# 2_cyber60-mxhs_matrix.net
KiCad netlist of a schematic drawn in Altium Designer
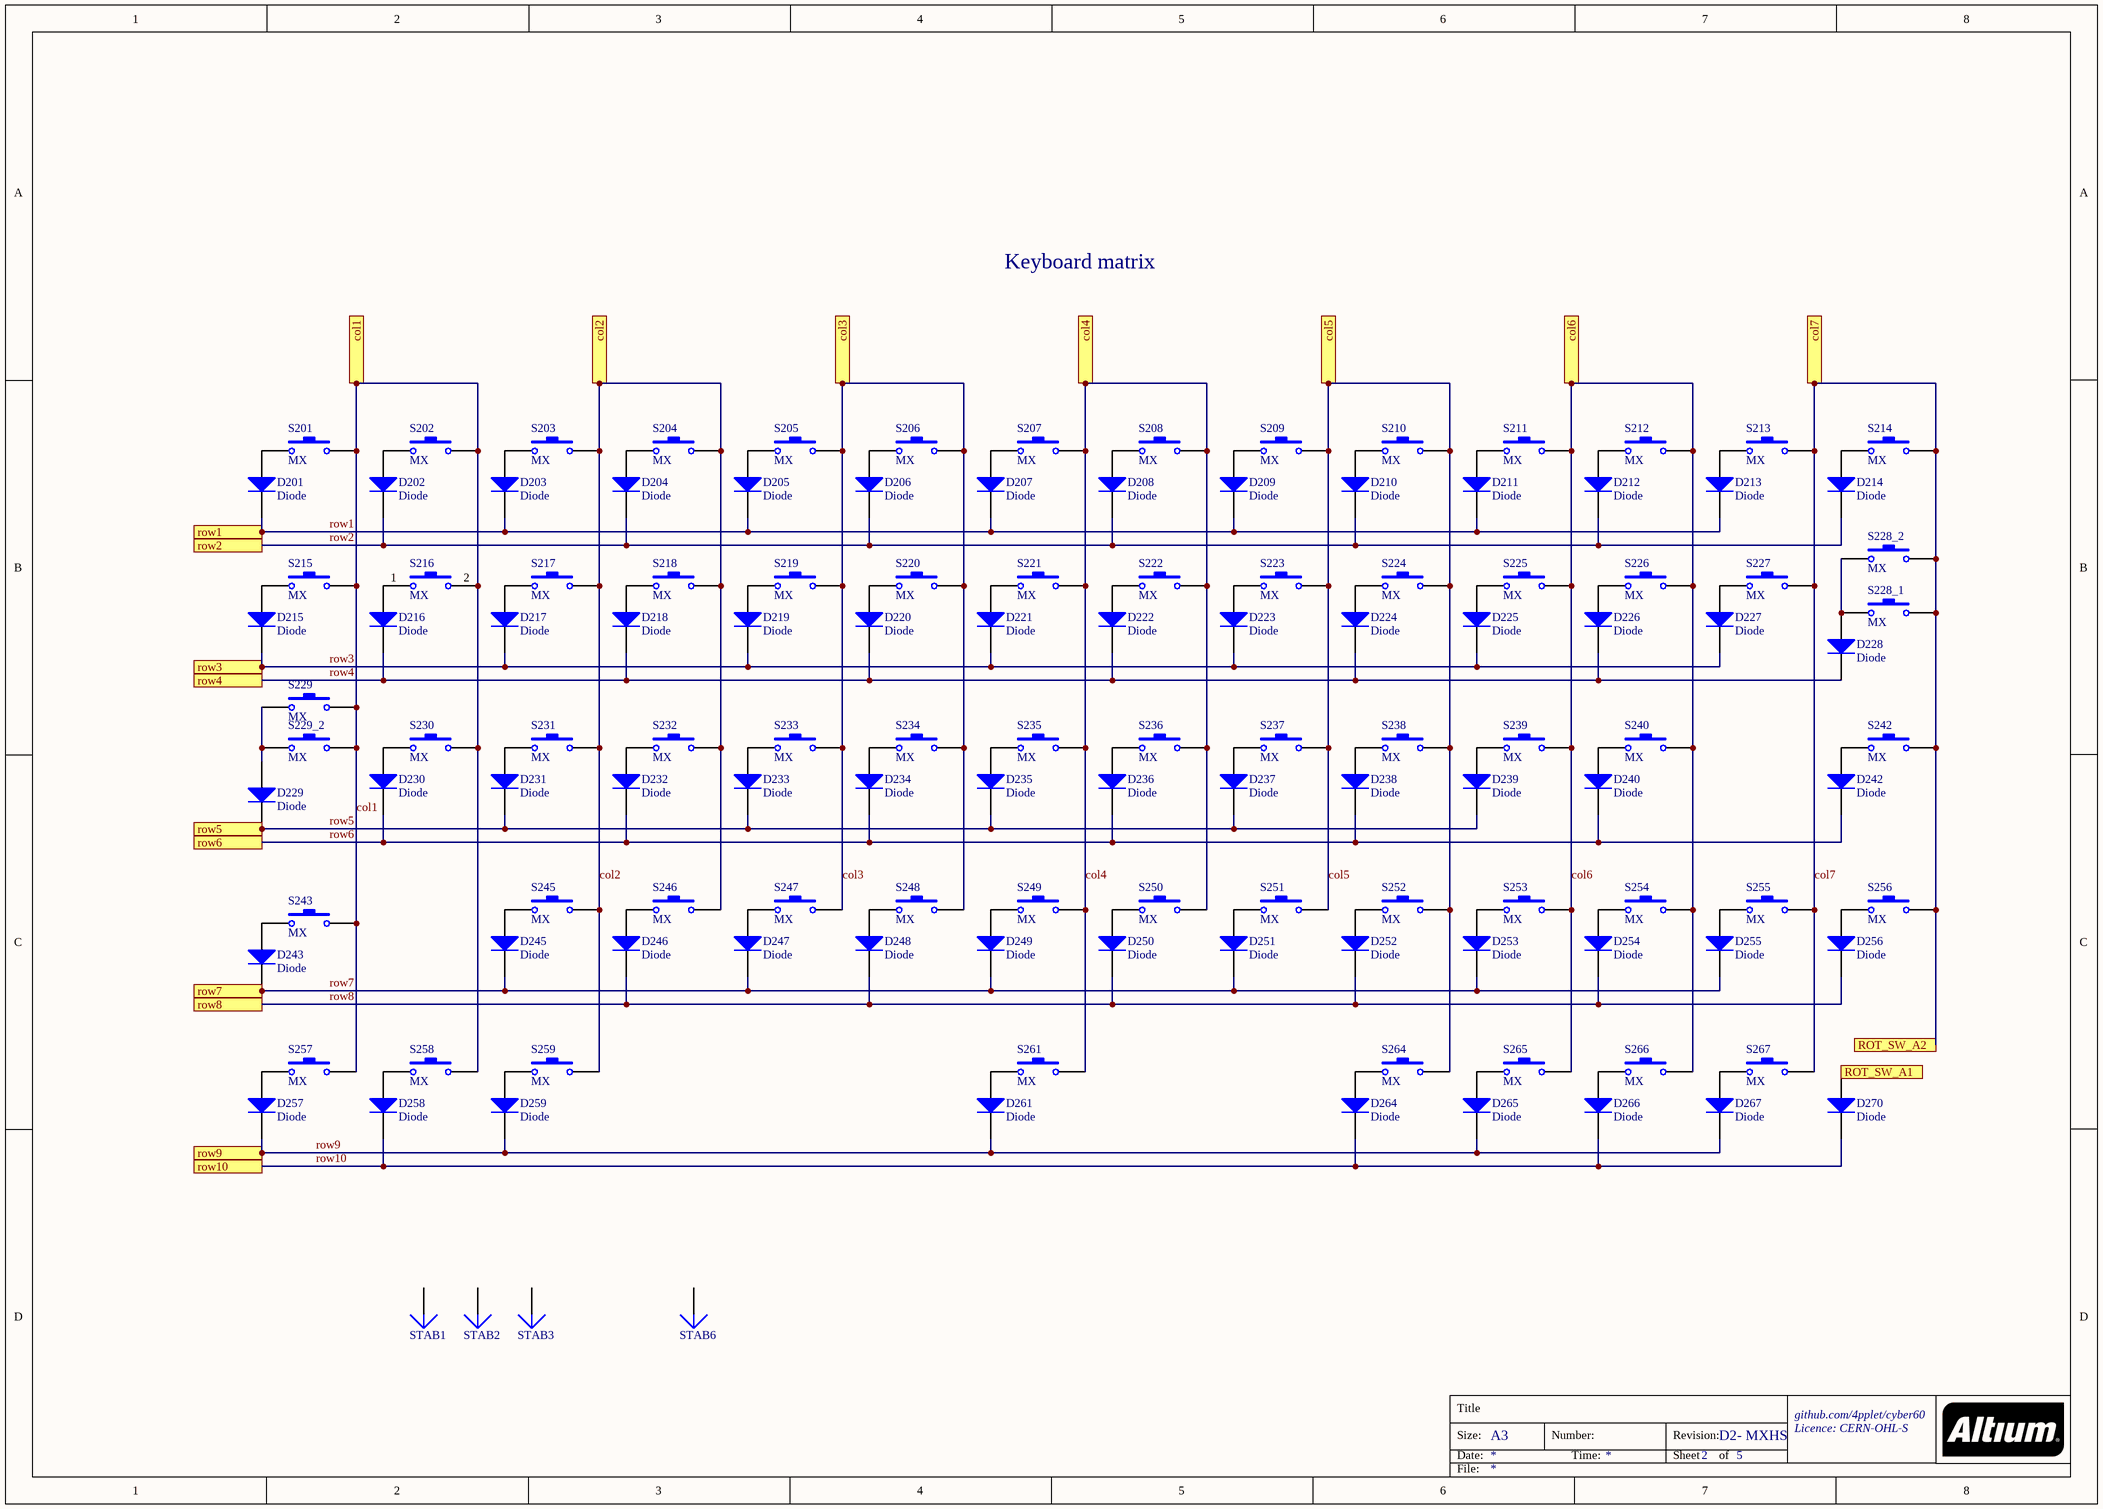
[diagram p0: 2_cyber60-mxhs_matrix.SchDoc]

(export (version "E")
  (design (tool "Eeschema 10.0.6"))
  (components
    (comp (ref "D201")
      (value "Diode")
      (footprint "SOD-123")
      (description "Default Diode")
      (fields (field (name "LCSC PART #") "C81598") (field (name "MRF.PART") "1N4148W"))
      (libsource (lib "Miscellaneous Devices") (part "Diode"))
    )
    (comp (ref "D202")
      (value "Diode")
      (footprint "SOD-123")
      (description "Default Diode")
      (fields (field (name "LCSC PART #") "C81598") (field (name "MRF.PART") "1N4148W"))
      (libsource (lib "Miscellaneous Devices") (part "Diode"))
    )
    (comp (ref "D203")
      (value "Diode")
      (footprint "SOD-123")
      (description "Default Diode")
      (fields (field (name "LCSC PART #") "C81598") (field (name "MRF.PART") "1N4148W"))
      (libsource (lib "Miscellaneous Devices") (part "Diode"))
    )
    (comp (ref "D204")
      (value "Diode")
      (footprint "SOD-123")
      (description "Default Diode")
      (fields (field (name "LCSC PART #") "C81598") (field (name "MRF.PART") "1N4148W"))
      (libsource (lib "Miscellaneous Devices") (part "Diode"))
    )
    (comp (ref "D205")
      (value "Diode")
      (footprint "SOD-123")
      (description "Default Diode")
      (fields (field (name "LCSC PART #") "C81598") (field (name "MRF.PART") "1N4148W"))
      (libsource (lib "Miscellaneous Devices") (part "Diode"))
    )
    (comp (ref "D206")
      (value "Diode")
      (footprint "SOD-123")
      (description "Default Diode")
      (fields (field (name "LCSC PART #") "C81598") (field (name "MRF.PART") "1N4148W"))
      (libsource (lib "Miscellaneous Devices") (part "Diode"))
    )
    (comp (ref "D207")
      (value "Diode")
      (footprint "SOD-123")
      (description "Default Diode")
      (fields (field (name "LCSC PART #") "C81598") (field (name "MRF.PART") "1N4148W"))
      (libsource (lib "Miscellaneous Devices") (part "Diode"))
    )
    (comp (ref "D208")
      (value "Diode")
      (footprint "SOD-123")
      (description "Default Diode")
      (fields (field (name "LCSC PART #") "C81598") (field (name "MRF.PART") "1N4148W"))
      (libsource (lib "Miscellaneous Devices") (part "Diode"))
    )
    (comp (ref "D209")
      (value "Diode")
      (footprint "SOD-123")
      (description "Default Diode")
      (fields (field (name "LCSC PART #") "C81598") (field (name "MRF.PART") "1N4148W"))
      (libsource (lib "Miscellaneous Devices") (part "Diode"))
    )
    (comp (ref "D210")
      (value "Diode")
      (footprint "SOD-123")
      (description "Default Diode")
      (fields (field (name "LCSC PART #") "C81598") (field (name "MRF.PART") "1N4148W"))
      (libsource (lib "Miscellaneous Devices") (part "Diode"))
    )
    (comp (ref "D211")
      (value "Diode")
      (footprint "SOD-123")
      (description "Default Diode")
      (fields (field (name "LCSC PART #") "C81598") (field (name "MRF.PART") "1N4148W"))
      (libsource (lib "Miscellaneous Devices") (part "Diode"))
    )
    (comp (ref "D212")
      (value "Diode")
      (footprint "SOD-123")
      (description "Default Diode")
      (fields (field (name "LCSC PART #") "C81598") (field (name "MRF.PART") "1N4148W"))
      (libsource (lib "Miscellaneous Devices") (part "Diode"))
    )
    (comp (ref "D213")
      (value "Diode")
      (footprint "SOD-123")
      (description "Default Diode")
      (fields (field (name "LCSC PART #") "C81598") (field (name "MRF.PART") "1N4148W"))
      (libsource (lib "Miscellaneous Devices") (part "Diode"))
    )
    (comp (ref "D214")
      (value "Diode")
      (footprint "SOD-123")
      (description "Default Diode")
      (fields (field (name "LCSC PART #") "C81598") (field (name "MRF.PART") "1N4148W"))
      (libsource (lib "Miscellaneous Devices") (part "Diode"))
    )
    (comp (ref "D215")
      (value "Diode")
      (footprint "SOD-123")
      (description "Default Diode")
      (fields (field (name "LCSC PART #") "C81598") (field (name "MRF.PART") "1N4148W"))
      (libsource (lib "Miscellaneous Devices") (part "Diode"))
    )
    (comp (ref "D216")
      (value "Diode")
      (footprint "SOD-123")
      (description "Default Diode")
      (fields (field (name "LCSC PART #") "C81598") (field (name "MRF.PART") "1N4148W"))
      (libsource (lib "Miscellaneous Devices") (part "Diode"))
    )
    (comp (ref "D217")
      (value "Diode")
      (footprint "SOD-123")
      (description "Default Diode")
      (fields (field (name "LCSC PART #") "C81598") (field (name "MRF.PART") "1N4148W"))
      (libsource (lib "Miscellaneous Devices") (part "Diode"))
    )
    (comp (ref "D218")
      (value "Diode")
      (footprint "SOD-123")
      (description "Default Diode")
      (fields (field (name "LCSC PART #") "C81598") (field (name "MRF.PART") "1N4148W"))
      (libsource (lib "Miscellaneous Devices") (part "Diode"))
    )
    (comp (ref "D219")
      (value "Diode")
      (footprint "SOD-123")
      (description "Default Diode")
      (fields (field (name "LCSC PART #") "C81598") (field (name "MRF.PART") "1N4148W"))
      (libsource (lib "Miscellaneous Devices") (part "Diode"))
    )
    (comp (ref "D220")
      (value "Diode")
      (footprint "SOD-123")
      (description "Default Diode")
      (fields (field (name "LCSC PART #") "C81598") (field (name "MRF.PART") "1N4148W"))
      (libsource (lib "Miscellaneous Devices") (part "Diode"))
    )
    (comp (ref "D221")
      (value "Diode")
      (footprint "SOD-123")
      (description "Default Diode")
      (fields (field (name "LCSC PART #") "C81598") (field (name "MRF.PART") "1N4148W"))
      (libsource (lib "Miscellaneous Devices") (part "Diode"))
    )
    (comp (ref "D222")
      (value "Diode")
      (footprint "SOD-123")
      (description "Default Diode")
      (fields (field (name "LCSC PART #") "C81598") (field (name "MRF.PART") "1N4148W"))
      (libsource (lib "Miscellaneous Devices") (part "Diode"))
    )
    (comp (ref "D223")
      (value "Diode")
      (footprint "SOD-123")
      (description "Default Diode")
      (fields (field (name "LCSC PART #") "C81598") (field (name "MRF.PART") "1N4148W"))
      (libsource (lib "Miscellaneous Devices") (part "Diode"))
    )
    (comp (ref "D224")
      (value "Diode")
      (footprint "SOD-123")
      (description "Default Diode")
      (fields (field (name "LCSC PART #") "C81598") (field (name "MRF.PART") "1N4148W"))
      (libsource (lib "Miscellaneous Devices") (part "Diode"))
    )
    (comp (ref "D225")
      (value "Diode")
      (footprint "SOD-123")
      (description "Default Diode")
      (fields (field (name "LCSC PART #") "C81598") (field (name "MRF.PART") "1N4148W"))
      (libsource (lib "Miscellaneous Devices") (part "Diode"))
    )
    (comp (ref "D226")
      (value "Diode")
      (footprint "SOD-123")
      (description "Default Diode")
      (fields (field (name "LCSC PART #") "C81598") (field (name "MRF.PART") "1N4148W"))
      (libsource (lib "Miscellaneous Devices") (part "Diode"))
    )
    (comp (ref "D227")
      (value "Diode")
      (footprint "SOD-123")
      (description "Default Diode")
      (fields (field (name "LCSC PART #") "C81598") (field (name "MRF.PART") "1N4148W"))
      (libsource (lib "Miscellaneous Devices") (part "Diode"))
    )
    (comp (ref "D228")
      (value "Diode")
      (footprint "SOD-123")
      (description "Default Diode")
      (fields (field (name "LCSC PART #") "C81598") (field (name "MRF.PART") "1N4148W"))
      (libsource (lib "Miscellaneous Devices") (part "Diode"))
    )
    (comp (ref "D229")
      (value "Diode")
      (footprint "SOD-123")
      (description "Default Diode")
      (fields (field (name "LCSC PART #") "C81598") (field (name "MRF.PART") "1N4148W"))
      (libsource (lib "Miscellaneous Devices") (part "Diode"))
    )
    (comp (ref "D230")
      (value "Diode")
      (footprint "SOD-123")
      (description "Default Diode")
      (fields (field (name "LCSC PART #") "C81598") (field (name "MRF.PART") "1N4148W"))
      (libsource (lib "Miscellaneous Devices") (part "Diode"))
    )
    (comp (ref "D231")
      (value "Diode")
      (footprint "SOD-123")
      (description "Default Diode")
      (fields (field (name "LCSC PART #") "C81598") (field (name "MRF.PART") "1N4148W"))
      (libsource (lib "Miscellaneous Devices") (part "Diode"))
    )
    (comp (ref "D232")
      (value "Diode")
      (footprint "SOD-123")
      (description "Default Diode")
      (fields (field (name "LCSC PART #") "C81598") (field (name "MRF.PART") "1N4148W"))
      (libsource (lib "Miscellaneous Devices") (part "Diode"))
    )
    (comp (ref "D233")
      (value "Diode")
      (footprint "SOD-123")
      (description "Default Diode")
      (fields (field (name "LCSC PART #") "C81598") (field (name "MRF.PART") "1N4148W"))
      (libsource (lib "Miscellaneous Devices") (part "Diode"))
    )
    (comp (ref "D234")
      (value "Diode")
      (footprint "SOD-123")
      (description "Default Diode")
      (fields (field (name "LCSC PART #") "C81598") (field (name "MRF.PART") "1N4148W"))
      (libsource (lib "Miscellaneous Devices") (part "Diode"))
    )
    (comp (ref "D235")
      (value "Diode")
      (footprint "SOD-123")
      (description "Default Diode")
      (fields (field (name "LCSC PART #") "C81598") (field (name "MRF.PART") "1N4148W"))
      (libsource (lib "Miscellaneous Devices") (part "Diode"))
    )
    (comp (ref "D236")
      (value "Diode")
      (footprint "SOD-123")
      (description "Default Diode")
      (fields (field (name "LCSC PART #") "C81598") (field (name "MRF.PART") "1N4148W"))
      (libsource (lib "Miscellaneous Devices") (part "Diode"))
    )
    (comp (ref "D237")
      (value "Diode")
      (footprint "SOD-123")
      (description "Default Diode")
      (fields (field (name "LCSC PART #") "C81598") (field (name "MRF.PART") "1N4148W"))
      (libsource (lib "Miscellaneous Devices") (part "Diode"))
    )
    (comp (ref "D238")
      (value "Diode")
      (footprint "SOD-123")
      (description "Default Diode")
      (fields (field (name "LCSC PART #") "C81598") (field (name "MRF.PART") "1N4148W"))
      (libsource (lib "Miscellaneous Devices") (part "Diode"))
    )
    (comp (ref "D239")
      (value "Diode")
      (footprint "SOD-123")
      (description "Default Diode")
      (fields (field (name "LCSC PART #") "C81598") (field (name "MRF.PART") "1N4148W"))
      (libsource (lib "Miscellaneous Devices") (part "Diode"))
    )
    (comp (ref "D240")
      (value "Diode")
      (footprint "SOD-123")
      (description "Default Diode")
      (fields (field (name "LCSC PART #") "C81598") (field (name "MRF.PART") "1N4148W"))
      (libsource (lib "Miscellaneous Devices") (part "Diode"))
    )
    (comp (ref "D242")
      (value "Diode")
      (footprint "SOD-123")
      (description "Default Diode")
      (fields (field (name "LCSC PART #") "C81598") (field (name "MRF.PART") "1N4148W"))
      (libsource (lib "Miscellaneous Devices") (part "Diode"))
    )
    (comp (ref "D243")
      (value "Diode")
      (footprint "SOD-123")
      (description "Default Diode")
      (fields (field (name "LCSC PART #") "C81598") (field (name "MRF.PART") "1N4148W"))
      (libsource (lib "Miscellaneous Devices") (part "Diode"))
    )
    (comp (ref "D245")
      (value "Diode")
      (footprint "SOD-123")
      (description "Default Diode")
      (fields (field (name "LCSC PART #") "C81598") (field (name "MRF.PART") "1N4148W"))
      (libsource (lib "Miscellaneous Devices") (part "Diode"))
    )
    (comp (ref "D246")
      (value "Diode")
      (footprint "SOD-123")
      (description "Default Diode")
      (fields (field (name "LCSC PART #") "C81598") (field (name "MRF.PART") "1N4148W"))
      (libsource (lib "Miscellaneous Devices") (part "Diode"))
    )
    (comp (ref "D247")
      (value "Diode")
      (footprint "SOD-123")
      (description "Default Diode")
      (fields (field (name "LCSC PART #") "C81598") (field (name "MRF.PART") "1N4148W"))
      (libsource (lib "Miscellaneous Devices") (part "Diode"))
    )
    (comp (ref "D248")
      (value "Diode")
      (footprint "SOD-123")
      (description "Default Diode")
      (fields (field (name "LCSC PART #") "C81598") (field (name "MRF.PART") "1N4148W"))
      (libsource (lib "Miscellaneous Devices") (part "Diode"))
    )
    (comp (ref "D249")
      (value "Diode")
      (footprint "SOD-123")
      (description "Default Diode")
      (fields (field (name "LCSC PART #") "C81598") (field (name "MRF.PART") "1N4148W"))
      (libsource (lib "Miscellaneous Devices") (part "Diode"))
    )
    (comp (ref "D250")
      (value "Diode")
      (footprint "SOD-123")
      (description "Default Diode")
      (fields (field (name "LCSC PART #") "C81598") (field (name "MRF.PART") "1N4148W"))
      (libsource (lib "Miscellaneous Devices") (part "Diode"))
    )
    (comp (ref "D251")
      (value "Diode")
      (footprint "SOD-123")
      (description "Default Diode")
      (fields (field (name "LCSC PART #") "C81598") (field (name "MRF.PART") "1N4148W"))
      (libsource (lib "Miscellaneous Devices") (part "Diode"))
    )
    (comp (ref "D252")
      (value "Diode")
      (footprint "SOD-123")
      (description "Default Diode")
      (fields (field (name "LCSC PART #") "C81598") (field (name "MRF.PART") "1N4148W"))
      (libsource (lib "Miscellaneous Devices") (part "Diode"))
    )
    (comp (ref "D253")
      (value "Diode")
      (footprint "SOD-123")
      (description "Default Diode")
      (fields (field (name "LCSC PART #") "C81598") (field (name "MRF.PART") "1N4148W"))
      (libsource (lib "Miscellaneous Devices") (part "Diode"))
    )
    (comp (ref "D254")
      (value "Diode")
      (footprint "SOD-123")
      (description "Default Diode")
      (fields (field (name "LCSC PART #") "C81598") (field (name "MRF.PART") "1N4148W"))
      (libsource (lib "Miscellaneous Devices") (part "Diode"))
    )
    (comp (ref "D255")
      (value "Diode")
      (footprint "SOD-123")
      (description "Default Diode")
      (fields (field (name "LCSC PART #") "C81598") (field (name "MRF.PART") "1N4148W"))
      (libsource (lib "Miscellaneous Devices") (part "Diode"))
    )
    (comp (ref "D256")
      (value "Diode")
      (footprint "SOD-123")
      (description "Default Diode")
      (fields (field (name "LCSC PART #") "C81598") (field (name "MRF.PART") "1N4148W"))
      (libsource (lib "Miscellaneous Devices") (part "Diode"))
    )
    (comp (ref "D257")
      (value "Diode")
      (footprint "SOD-123")
      (description "Default Diode")
      (fields (field (name "LCSC PART #") "C81598") (field (name "MRF.PART") "1N4148W"))
      (libsource (lib "Miscellaneous Devices") (part "Diode"))
    )
    (comp (ref "D258")
      (value "Diode")
      (footprint "SOD-123")
      (description "Default Diode")
      (fields (field (name "LCSC PART #") "C81598") (field (name "MRF.PART") "1N4148W"))
      (libsource (lib "Miscellaneous Devices") (part "Diode"))
    )
    (comp (ref "D259")
      (value "Diode")
      (footprint "SOD-123")
      (description "Default Diode")
      (fields (field (name "LCSC PART #") "C81598") (field (name "MRF.PART") "1N4148W"))
      (libsource (lib "Miscellaneous Devices") (part "Diode"))
    )
    (comp (ref "D261")
      (value "Diode")
      (footprint "SOD-123")
      (description "Default Diode")
      (fields (field (name "LCSC PART #") "C81598") (field (name "MRF.PART") "1N4148W"))
      (libsource (lib "Miscellaneous Devices") (part "Diode"))
    )
    (comp (ref "D264")
      (value "Diode")
      (footprint "SOD-123")
      (description "Default Diode")
      (fields (field (name "LCSC PART #") "C81598") (field (name "MRF.PART") "1N4148W"))
      (libsource (lib "Miscellaneous Devices") (part "Diode"))
    )
    (comp (ref "D265")
      (value "Diode")
      (footprint "SOD-123")
      (description "Default Diode")
      (fields (field (name "LCSC PART #") "C81598") (field (name "MRF.PART") "1N4148W"))
      (libsource (lib "Miscellaneous Devices") (part "Diode"))
    )
    (comp (ref "D266")
      (value "Diode")
      (footprint "SOD-123")
      (description "Default Diode")
      (fields (field (name "LCSC PART #") "C81598") (field (name "MRF.PART") "1N4148W"))
      (libsource (lib "Miscellaneous Devices") (part "Diode"))
    )
    (comp (ref "D267")
      (value "Diode")
      (footprint "SOD-123")
      (description "Default Diode")
      (fields (field (name "LCSC PART #") "C81598") (field (name "MRF.PART") "1N4148W"))
      (libsource (lib "Miscellaneous Devices") (part "Diode"))
    )
    (comp (ref "D270")
      (value "Diode")
      (footprint "SOD-123")
      (description "Default Diode")
      (fields (field (name "LCSC PART #") "C81598") (field (name "MRF.PART") "1N4148W"))
      (libsource (lib "Miscellaneous Devices") (part "Diode"))
    )
    (comp (ref "S201")
      (value "MX")
      (footprint "MXHS-switch - 1U Top layer - switched pol AS2")
      (description "Switch")
      (fields (field (name "LCSC PART #") "C2803348") (field (name "MRF.PART") "CPG151101S11"))
      (libsource (lib "Miscellaneous Devices") (part "SW-PB"))
    )
    (comp (ref "S202")
      (value "MX")
      (footprint "MXHS-switch - 1U Top layer - switched pol AS2")
      (description "Switch")
      (fields (field (name "LCSC PART #") "C2803348") (field (name "MRF.PART") "CPG151101S11"))
      (libsource (lib "Miscellaneous Devices") (part "SW-PB"))
    )
    (comp (ref "S203")
      (value "MX")
      (footprint "MXHS-switch - 1U Top layer - AS2")
      (description "Switch")
      (fields (field (name "LCSC PART #") "C2803348") (field (name "MRF.PART") "CPG151101S11"))
      (libsource (lib "Miscellaneous Devices") (part "SW-PB"))
    )
    (comp (ref "S204")
      (value "MX")
      (footprint "MXHS-switch - 1U Top layer - switched pol AS2")
      (description "Switch")
      (fields (field (name "LCSC PART #") "C2803348") (field (name "MRF.PART") "CPG151101S11"))
      (libsource (lib "Miscellaneous Devices") (part "SW-PB"))
    )
    (comp (ref "S205")
      (value "MX")
      (footprint "MXHS-switch - 1U Top layer - AS2")
      (description "Switch")
      (fields (field (name "LCSC PART #") "C2803348") (field (name "MRF.PART") "CPG151101S11"))
      (libsource (lib "Miscellaneous Devices") (part "SW-PB"))
    )
    (comp (ref "S206")
      (value "MX")
      (footprint "MXHS-switch - 1U Top layer - AS2")
      (description "Switch")
      (fields (field (name "LCSC PART #") "C2803348") (field (name "MRF.PART") "CPG151101S11"))
      (libsource (lib "Miscellaneous Devices") (part "SW-PB"))
    )
    (comp (ref "S207")
      (value "MX")
      (footprint "MXHS-switch - 1U Top layer - AS2")
      (description "Switch")
      (fields (field (name "LCSC PART #") "C2803348") (field (name "MRF.PART") "CPG151101S11"))
      (libsource (lib "Miscellaneous Devices") (part "SW-PB"))
    )
    (comp (ref "S208")
      (value "MX")
      (footprint "MXHS-switch - 1U Top layer - AS2")
      (description "Switch")
      (fields (field (name "LCSC PART #") "C2803348") (field (name "MRF.PART") "CPG151101S11"))
      (libsource (lib "Miscellaneous Devices") (part "SW-PB"))
    )
    (comp (ref "S209")
      (value "MX")
      (footprint "MXHS-switch - 1U Top layer - AS2")
      (description "Switch")
      (fields (field (name "LCSC PART #") "C2803348") (field (name "MRF.PART") "CPG151101S11"))
      (libsource (lib "Miscellaneous Devices") (part "SW-PB"))
    )
    (comp (ref "S210")
      (value "MX")
      (footprint "MXHS-switch - 1U Top layer - switched pol AS2")
      (description "Switch")
      (fields (field (name "LCSC PART #") "C2803348") (field (name "MRF.PART") "CPG151101S11"))
      (libsource (lib "Miscellaneous Devices") (part "SW-PB"))
    )
    (comp (ref "S211")
      (value "MX")
      (footprint "MXHS-switch - 1U Top layer - AS2")
      (description "Switch")
      (fields (field (name "LCSC PART #") "C2803348") (field (name "MRF.PART") "CPG151101S11"))
      (libsource (lib "Miscellaneous Devices") (part "SW-PB"))
    )
    (comp (ref "S212")
      (value "MX")
      (footprint "MXHS-switch - 1U Top layer - AS2")
      (description "Switch")
      (fields (field (name "LCSC PART #") "C2803348") (field (name "MRF.PART") "CPG151101S11"))
      (libsource (lib "Miscellaneous Devices") (part "SW-PB"))
    )
    (comp (ref "S213")
      (value "MX")
      (footprint "MXHS-switch - 1U Top layer - switched pol AS2")
      (description "Switch")
      (fields (field (name "LCSC PART #") "C2803348") (field (name "MRF.PART") "CPG151101S11"))
      (libsource (lib "Miscellaneous Devices") (part "SW-PB"))
    )
    (comp (ref "S214")
      (value "MX")
      (footprint "MXHS-switch - 1U Top layer - AS2 - S2")
      (description "Switch")
      (fields (field (name "LCSC PART #") "C2803348") (field (name "MRF.PART") "CPG151101S11"))
      (libsource (lib "Miscellaneous Devices") (part "SW-PB"))
    )
    (comp (ref "S215")
      (value "MX")
      (footprint "MXHS-switch - 1U Top layer - switched pol AS2")
      (description "TAB")
      (fields (field (name "LCSC PART #") "C2803348") (field (name "MRF.PART") "CPG151101S11"))
      (libsource (lib "Miscellaneous Devices") (part "SW-PB"))
    )
    (comp (ref "S216")
      (value "MX")
      (footprint "MXHS-switch - 1U Top layer - AS2 - S1")
      (description "Switch")
      (fields (field (name "LCSC PART #") "C2803348") (field (name "MRF.PART") "CPG151101S11"))
      (libsource (lib "") (part "SW-PB_1"))
    )
    (comp (ref "S217")
      (value "MX")
      (footprint "MXHS-switch - 1U Top layer - AS2")
      (description "Switch")
      (fields (field (name "LCSC PART #") "C2803348") (field (name "MRF.PART") "CPG151101S11"))
      (libsource (lib "Miscellaneous Devices") (part "SW-PB"))
    )
    (comp (ref "S218")
      (value "MX")
      (footprint "MXHS-switch - 1U Top layer - AS2")
      (description "Switch")
      (fields (field (name "LCSC PART #") "C2803348") (field (name "MRF.PART") "CPG151101S11"))
      (libsource (lib "Miscellaneous Devices") (part "SW-PB"))
    )
    (comp (ref "S219")
      (value "MX")
      (footprint "MXHS-switch - 1U Top layer - AS2")
      (description "Switch")
      (fields (field (name "LCSC PART #") "C2803348") (field (name "MRF.PART") "CPG151101S11"))
      (libsource (lib "Miscellaneous Devices") (part "SW-PB"))
    )
    (comp (ref "S220")
      (value "MX")
      (footprint "MXHS-switch - 1U Top layer - switched pol AS2")
      (description "Switch")
      (fields (field (name "LCSC PART #") "C2803348") (field (name "MRF.PART") "CPG151101S11"))
      (libsource (lib "Miscellaneous Devices") (part "SW-PB"))
    )
    (comp (ref "S221")
      (value "MX")
      (footprint "MXHS-switch - 1U Top layer - switched pol AS2")
      (description "Switch")
      (fields (field (name "LCSC PART #") "C2803348") (field (name "MRF.PART") "CPG151101S11"))
      (libsource (lib "Miscellaneous Devices") (part "SW-PB"))
    )
    (comp (ref "S222")
      (value "MX")
      (footprint "MXHS-switch - 1U Top layer - AS2")
      (description "Switch")
      (fields (field (name "LCSC PART #") "C2803348") (field (name "MRF.PART") "CPG151101S11"))
      (libsource (lib "Miscellaneous Devices") (part "SW-PB"))
    )
    (comp (ref "S223")
      (value "MX")
      (footprint "MXHS-switch - 1U Top layer - AS2")
      (description "Switch")
      (fields (field (name "LCSC PART #") "C2803348") (field (name "MRF.PART") "CPG151101S11"))
      (libsource (lib "Miscellaneous Devices") (part "SW-PB"))
    )
    (comp (ref "S224")
      (value "MX")
      (footprint "MXHS-switch - 1U Top layer - AS2")
      (description "Switch")
      (fields (field (name "LCSC PART #") "C2803348") (field (name "MRF.PART") "CPG151101S11"))
      (libsource (lib "Miscellaneous Devices") (part "SW-PB"))
    )
    (comp (ref "S225")
      (value "MX")
      (footprint "MXHS-switch - 1U Top layer - AS2")
      (description "Switch")
      (fields (field (name "LCSC PART #") "C2803348") (field (name "MRF.PART") "CPG151101S11"))
      (libsource (lib "Miscellaneous Devices") (part "SW-PB"))
    )
    (comp (ref "S226")
      (value "MX")
      (footprint "MXHS-switch - 1U Top layer - switched pol AS2")
      (description "Switch")
      (fields (field (name "LCSC PART #") "C2803348") (field (name "MRF.PART") "CPG151101S11"))
      (libsource (lib "Miscellaneous Devices") (part "SW-PB"))
    )
    (comp (ref "S227")
      (value "MX")
      (footprint "MXHS-switch - 1U Top layer - switched pol AS2")
      (description "Switch")
      (fields (field (name "LCSC PART #") "C2803348") (field (name "MRF.PART") "CPG151101S11"))
      (libsource (lib "Miscellaneous Devices") (part "SW-PB"))
    )
    (comp (ref "S228_1")
      (value "MX")
      (footprint "MXHS-switch - 1U Top layer - AS2 - S1")
      (description "Switch")
      (fields (field (name "LCSC PART #") "C2803348") (field (name "MRF.PART") "CPG151101S11"))
      (libsource (lib "Miscellaneous Devices") (part "SW-PB"))
    )
    (comp (ref "S228_2")
      (value "MX")
      (footprint "MXHS-switch - 1U Top layer - AS2 - S2")
      (description "Switch")
      (fields (field (name "LCSC PART #") "C2803348") (field (name "MRF.PART") "CPG151101S11"))
      (libsource (lib "Miscellaneous Devices") (part "SW-PB"))
    )
    (comp (ref "S229")
      (value "MX")
      (footprint "MXHS-switch - 1U Top layer - AS2")
      (description "Switch")
      (fields (field (name "LCSC PART #") "C2803348") (field (name "MRF.PART") "CPG151101S11"))
      (libsource (lib "Miscellaneous Devices") (part "SW-PB"))
    )
    (comp (ref "S229_2")
      (value "MX")
      (footprint "MXHS-switch - 1U Top layer - switched pol AS2")
      (description "Switch")
      (fields (field (name "LCSC PART #") "C2803348") (field (name "MRF.PART") "CPG151101S11"))
      (libsource (lib "Miscellaneous Devices") (part "SW-PB"))
    )
    (comp (ref "S230")
      (value "MX")
      (footprint "MXHS-switch - 1U Top layer - AS2")
      (description "Switch")
      (fields (field (name "LCSC PART #") "C2803348") (field (name "MRF.PART") "CPG151101S11"))
      (libsource (lib "Miscellaneous Devices") (part "SW-PB"))
    )
    (comp (ref "S231")
      (value "MX")
      (footprint "MXHS-switch - 1U Top layer - AS2")
      (description "Switch")
      (fields (field (name "LCSC PART #") "C2803348") (field (name "MRF.PART") "CPG151101S11"))
      (libsource (lib "Miscellaneous Devices") (part "SW-PB"))
    )
    (comp (ref "S232")
      (value "MX")
      (footprint "MXHS-switch - 1U Top layer - AS2")
      (description "Switch")
      (fields (field (name "LCSC PART #") "C2803348") (field (name "MRF.PART") "CPG151101S11"))
      (libsource (lib "Miscellaneous Devices") (part "SW-PB"))
    )
    (comp (ref "S233")
      (value "MX")
      (footprint "MXHS-switch - 1U Top layer - AS2")
      (description "Switch")
      (fields (field (name "LCSC PART #") "C2803348") (field (name "MRF.PART") "CPG151101S11"))
      (libsource (lib "Miscellaneous Devices") (part "SW-PB"))
    )
    (comp (ref "S234")
      (value "MX")
      (footprint "MXHS-switch - 1U Top layer - switched pol AS2")
      (description "Switch")
      (fields (field (name "LCSC PART #") "C2803348") (field (name "MRF.PART") "CPG151101S11"))
      (libsource (lib "Miscellaneous Devices") (part "SW-PB"))
    )
    (comp (ref "S235")
      (value "MX")
      (footprint "MXHS-switch - 1U Top layer - AS2 - S2")
      (description "Switch")
      (fields (field (name "LCSC PART #") "C2803348") (field (name "MRF.PART") "CPG151101S11"))
      (libsource (lib "Miscellaneous Devices") (part "SW-PB"))
    )
    (comp (ref "S236")
      (value "MX")
      (footprint "MXHS-switch - 1U Top layer - AS2")
      (description "Switch")
      (fields (field (name "LCSC PART #") "C2803348") (field (name "MRF.PART") "CPG151101S11"))
      (libsource (lib "Miscellaneous Devices") (part "SW-PB"))
    )
    (comp (ref "S237")
      (value "MX")
      (footprint "MXHS-switch - 1U Top layer - AS2")
      (description "Switch")
      (fields (field (name "LCSC PART #") "C2803348") (field (name "MRF.PART") "CPG151101S11"))
      (libsource (lib "Miscellaneous Devices") (part "SW-PB"))
    )
    (comp (ref "S238")
      (value "MX")
      (footprint "MXHS-switch - 1U Top layer - AS2")
      (description "Switch")
      (fields (field (name "LCSC PART #") "C2803348") (field (name "MRF.PART") "CPG151101S11"))
      (libsource (lib "Miscellaneous Devices") (part "SW-PB"))
    )
    (comp (ref "S239")
      (value "MX")
      (footprint "MXHS-switch - 1U Top layer - switched pol AS2")
      (description "Switch")
      (fields (field (name "LCSC PART #") "C2803348") (field (name "MRF.PART") "CPG151101S11"))
      (libsource (lib "Miscellaneous Devices") (part "SW-PB"))
    )
    (comp (ref "S240")
      (value "MX")
      (footprint "MXHS-switch - 1U Top layer - AS2")
      (description "Switch")
      (fields (field (name "LCSC PART #") "C2803348") (field (name "MRF.PART") "CPG151101S11"))
      (libsource (lib "Miscellaneous Devices") (part "SW-PB"))
    )
    (comp (ref "S242")
      (value "MX")
      (footprint "MXHS-switch - 1U Top layer - AS2 - S2")
      (description "Switch")
      (fields (field (name "LCSC PART #") "C2803348") (field (name "MRF.PART") "CPG151101S11"))
      (libsource (lib "Miscellaneous Devices") (part "SW-PB"))
    )
    (comp (ref "S243")
      (value "MX")
      (footprint "MXHS-switch - 1U Top layer - AS2")
      (description "Switch")
      (fields (field (name "LCSC PART #") "C2803348") (field (name "MRF.PART") "CPG151101S11"))
      (libsource (lib "Miscellaneous Devices") (part "SW-PB"))
    )
    (comp (ref "S245")
      (value "MX")
      (footprint "MXHS-switch - 1U Top layer - AS2")
      (description "Switch")
      (fields (field (name "LCSC PART #") "C2803348") (field (name "MRF.PART") "CPG151101S11"))
      (libsource (lib "Miscellaneous Devices") (part "SW-PB"))
    )
    (comp (ref "S246")
      (value "MX")
      (footprint "MXHS-switch - 1U Top layer - AS2")
      (description "Switch")
      (fields (field (name "LCSC PART #") "C2803348") (field (name "MRF.PART") "CPG151101S11"))
      (libsource (lib "Miscellaneous Devices") (part "SW-PB"))
    )
    (comp (ref "S247")
      (value "MX")
      (footprint "MXHS-switch - 1U Top layer - AS2")
      (description "Switch")
      (fields (field (name "LCSC PART #") "C2803348") (field (name "MRF.PART") "CPG151101S11"))
      (libsource (lib "Miscellaneous Devices") (part "SW-PB"))
    )
    (comp (ref "S248")
      (value "MX")
      (footprint "MXHS-switch - 1U Top layer - switched pol AS2")
      (description "Switch")
      (fields (field (name "LCSC PART #") "C2803348") (field (name "MRF.PART") "CPG151101S11"))
      (libsource (lib "Miscellaneous Devices") (part "SW-PB"))
    )
    (comp (ref "S249")
      (value "MX")
      (footprint "MXHS-switch - 1U Top layer - switched pol AS2")
      (description "Switch")
      (fields (field (name "LCSC PART #") "C2803348") (field (name "MRF.PART") "CPG151101S11"))
      (libsource (lib "Miscellaneous Devices") (part "SW-PB"))
    )
    (comp (ref "S250")
      (value "MX")
      (footprint "MXHS-switch - 1U Top layer - switched pol AS2")
      (description "Switch")
      (fields (field (name "LCSC PART #") "C2803348") (field (name "MRF.PART") "CPG151101S11"))
      (libsource (lib "Miscellaneous Devices") (part "SW-PB"))
    )
    (comp (ref "S251")
      (value "MX")
      (footprint "MXHS-switch - 1U Top layer - AS2")
      (description "Switch")
      (fields (field (name "LCSC PART #") "C2803348") (field (name "MRF.PART") "CPG151101S11"))
      (libsource (lib "Miscellaneous Devices") (part "SW-PB"))
    )
    (comp (ref "S252")
      (value "MX")
      (footprint "MXHS-switch - 1U Top layer - AS2")
      (description "Switch")
      (fields (field (name "LCSC PART #") "C2803348") (field (name "MRF.PART") "CPG151101S11"))
      (libsource (lib "Miscellaneous Devices") (part "SW-PB"))
    )
    (comp (ref "S253")
      (value "MX")
      (footprint "MXHS-switch - 1U Top layer - AS2")
      (description "Switch")
      (fields (field (name "LCSC PART #") "C2803348") (field (name "MRF.PART") "CPG151101S11"))
      (libsource (lib "Miscellaneous Devices") (part "SW-PB"))
    )
    (comp (ref "S254")
      (value "MX")
      (footprint "MXHS-switch - 1U Top layer - AS2")
      (description "Switch")
      (fields (field (name "LCSC PART #") "C2803348") (field (name "MRF.PART") "CPG151101S11"))
      (libsource (lib "Miscellaneous Devices") (part "SW-PB"))
    )
    (comp (ref "S255")
      (value "MX")
      (footprint "MXHS-switch - 1U Top layer - switched pol AS2")
      (description "Switch")
      (fields (field (name "LCSC PART #") "C2803348") (field (name "MRF.PART") "CPG151101S11"))
      (libsource (lib "Miscellaneous Devices") (part "SW-PB"))
    )
    (comp (ref "S256")
      (value "MX")
      (footprint "MXHS-switch - 1U Top layer - switched pol AS2")
      (description "Switch")
      (fields (field (name "LCSC PART #") "C2803348") (field (name "MRF.PART") "CPG151101S11"))
      (libsource (lib "Miscellaneous Devices") (part "SW-PB"))
    )
    (comp (ref "S257")
      (value "MX")
      (footprint "MXHS-switch - 1U Top layer - AS2")
      (description "Switch")
      (fields (field (name "LCSC PART #") "C2803348") (field (name "MRF.PART") "CPG151101S11"))
      (libsource (lib "Miscellaneous Devices") (part "SW-PB"))
    )
    (comp (ref "S258")
      (value "MX")
      (footprint "MXHS-switch - 1U Top layer - AS2")
      (description "Switch")
      (fields (field (name "LCSC PART #") "C2803348") (field (name "MRF.PART") "CPG151101S11"))
      (libsource (lib "Miscellaneous Devices") (part "SW-PB"))
    )
    (comp (ref "S259")
      (value "MX")
      (footprint "MXHS-switch - 1U Top layer - AS2")
      (description "Switch")
      (fields (field (name "LCSC PART #") "C2803348") (field (name "MRF.PART") "CPG151101S11"))
      (libsource (lib "Miscellaneous Devices") (part "SW-PB"))
    )
    (comp (ref "S261")
      (value "MX")
      (footprint "MXHS-switch - 1U Top layer - AS2")
      (description "Switch")
      (fields (field (name "LCSC PART #") "C2803348") (field (name "MRF.PART") "CPG151101S11"))
      (libsource (lib "Miscellaneous Devices") (part "SW-PB"))
    )
    (comp (ref "S264")
      (value "MX")
      (footprint "MXHS-switch - 1U Top layer - switched pol AS2")
      (description "Switch")
      (fields (field (name "LCSC PART #") "C2803348") (field (name "MRF.PART") "CPG151101S11"))
      (libsource (lib "Miscellaneous Devices") (part "SW-PB"))
    )
    (comp (ref "S265")
      (value "MX")
      (footprint "MXHS-switch - 1U Top layer - switched pol AS2")
      (description "Switch")
      (fields (field (name "LCSC PART #") "C2803348") (field (name "MRF.PART") "CPG151101S11"))
      (libsource (lib "Miscellaneous Devices") (part "SW-PB"))
    )
    (comp (ref "S266")
      (value "MX")
      (footprint "MXHS-switch - 1U Top layer - switched pol AS2")
      (description "Switch")
      (fields (field (name "LCSC PART #") "C2803348") (field (name "MRF.PART") "CPG151101S11"))
      (libsource (lib "Miscellaneous Devices") (part "SW-PB"))
    )
    (comp (ref "S267")
      (value "MX")
      (footprint "MXHS-switch - 1U Top layer - AS2")
      (description "Switch")
      (fields (field (name "LCSC PART #") "C2803348") (field (name "MRF.PART") "CPG151101S11"))
      (libsource (lib "Miscellaneous Devices") (part "SW-PB"))
    )
    (comp (ref "STAB1")
      (value "Plug")
      (footprint "Stab 2u")
      (libsource (lib "Miscellaneous Connectors") (part "Plug"))
    )
    (comp (ref "STAB2")
      (value "Plug")
      (footprint "Stab 2u")
      (libsource (lib "Miscellaneous Connectors") (part "Plug"))
    )
    (comp (ref "STAB3")
      (value "Plug")
      (footprint "Stab 7U")
      (libsource (lib "Miscellaneous Connectors") (part "Plug"))
    )
    (comp (ref "STAB6")
      (value "Plug")
      (footprint "Stab 2u")
      (libsource (lib "Miscellaneous Connectors") (part "Plug"))
    )
  )
  (nets
    (net (code "1") (name "/ROT_SW_A1") (class "Default")
      (node (ref "D270") (pin "1") (pinfunction "A_1") (pintype "passive"))
    )
    (net (code "2") (name "/col1") (class "Default")
      (node (ref "S201") (pin "2") (pinfunction "2_2") (pintype "passive"))
      (node (ref "S202") (pin "2") (pinfunction "2_2") (pintype "passive"))
      (node (ref "S215") (pin "2") (pinfunction "2_2") (pintype "passive"))
      (node (ref "S216") (pin "2") (pinfunction "2_2") (pintype "passive"))
      (node (ref "S229") (pin "2") (pinfunction "2_2") (pintype "passive"))
      (node (ref "S229_2") (pin "2") (pinfunction "2_2") (pintype "passive"))
      (node (ref "S230") (pin "2") (pinfunction "2_2") (pintype "passive"))
      (node (ref "S243") (pin "2") (pinfunction "2_2") (pintype "passive"))
      (node (ref "S257") (pin "2") (pinfunction "2_2") (pintype "passive"))
      (node (ref "S258") (pin "2") (pinfunction "2_2") (pintype "passive"))
    )
    (net (code "3") (name "/col2") (class "Default")
      (node (ref "S203") (pin "2") (pinfunction "2_2") (pintype "passive"))
      (node (ref "S204") (pin "2") (pinfunction "2_2") (pintype "passive"))
      (node (ref "S217") (pin "2") (pinfunction "2_2") (pintype "passive"))
      (node (ref "S218") (pin "2") (pinfunction "2_2") (pintype "passive"))
      (node (ref "S231") (pin "2") (pinfunction "2_2") (pintype "passive"))
      (node (ref "S232") (pin "2") (pinfunction "2_2") (pintype "passive"))
      (node (ref "S245") (pin "2") (pinfunction "2_2") (pintype "passive"))
      (node (ref "S246") (pin "2") (pinfunction "2_2") (pintype "passive"))
      (node (ref "S259") (pin "2") (pinfunction "2_2") (pintype "passive"))
    )
    (net (code "4") (name "/col3") (class "Default")
      (node (ref "S205") (pin "2") (pinfunction "2_2") (pintype "passive"))
      (node (ref "S206") (pin "2") (pinfunction "2_2") (pintype "passive"))
      (node (ref "S219") (pin "2") (pinfunction "2_2") (pintype "passive"))
      (node (ref "S220") (pin "2") (pinfunction "2_2") (pintype "passive"))
      (node (ref "S233") (pin "2") (pinfunction "2_2") (pintype "passive"))
      (node (ref "S234") (pin "2") (pinfunction "2_2") (pintype "passive"))
      (node (ref "S247") (pin "2") (pinfunction "2_2") (pintype "passive"))
      (node (ref "S248") (pin "2") (pinfunction "2_2") (pintype "passive"))
    )
    (net (code "5") (name "/col4") (class "Default")
      (node (ref "S207") (pin "2") (pinfunction "2_2") (pintype "passive"))
      (node (ref "S208") (pin "2") (pinfunction "2_2") (pintype "passive"))
      (node (ref "S221") (pin "2") (pinfunction "2_2") (pintype "passive"))
      (node (ref "S222") (pin "2") (pinfunction "2_2") (pintype "passive"))
      (node (ref "S235") (pin "2") (pinfunction "2_2") (pintype "passive"))
      (node (ref "S236") (pin "2") (pinfunction "2_2") (pintype "passive"))
      (node (ref "S249") (pin "2") (pinfunction "2_2") (pintype "passive"))
      (node (ref "S250") (pin "2") (pinfunction "2_2") (pintype "passive"))
      (node (ref "S261") (pin "1") (pinfunction "1_1") (pintype "passive"))
    )
    (net (code "6") (name "/col5") (class "Default")
      (node (ref "S209") (pin "2") (pinfunction "2_2") (pintype "passive"))
      (node (ref "S210") (pin "2") (pinfunction "2_2") (pintype "passive"))
      (node (ref "S223") (pin "2") (pinfunction "2_2") (pintype "passive"))
      (node (ref "S224") (pin "2") (pinfunction "2_2") (pintype "passive"))
      (node (ref "S237") (pin "2") (pinfunction "2_2") (pintype "passive"))
      (node (ref "S238") (pin "2") (pinfunction "2_2") (pintype "passive"))
      (node (ref "S251") (pin "2") (pinfunction "2_2") (pintype "passive"))
      (node (ref "S252") (pin "2") (pinfunction "2_2") (pintype "passive"))
      (node (ref "S264") (pin "1") (pinfunction "1_1") (pintype "passive"))
    )
    (net (code "7") (name "/col6") (class "Default")
      (node (ref "S211") (pin "2") (pinfunction "2_2") (pintype "passive"))
      (node (ref "S212") (pin "2") (pinfunction "2_2") (pintype "passive"))
      (node (ref "S225") (pin "2") (pinfunction "2_2") (pintype "passive"))
      (node (ref "S226") (pin "2") (pinfunction "2_2") (pintype "passive"))
      (node (ref "S239") (pin "2") (pinfunction "2_2") (pintype "passive"))
      (node (ref "S240") (pin "2") (pinfunction "2_2") (pintype "passive"))
      (node (ref "S253") (pin "2") (pinfunction "2_2") (pintype "passive"))
      (node (ref "S254") (pin "2") (pinfunction "2_2") (pintype "passive"))
      (node (ref "S265") (pin "2") (pinfunction "2_2") (pintype "passive"))
      (node (ref "S266") (pin "2") (pinfunction "2_2") (pintype "passive"))
    )
    (net (code "8") (name "/col7") (class "Default")
      (node (ref "S213") (pin "2") (pinfunction "2_2") (pintype "passive"))
      (node (ref "S214") (pin "2") (pinfunction "2_2") (pintype "passive"))
      (node (ref "S227") (pin "2") (pinfunction "2_2") (pintype "passive"))
      (node (ref "S228_1") (pin "2") (pinfunction "2_2") (pintype "passive"))
      (node (ref "S228_2") (pin "1") (pinfunction "1_1") (pintype "passive"))
      (node (ref "S242") (pin "1") (pinfunction "1_1") (pintype "passive"))
      (node (ref "S255") (pin "2") (pinfunction "2_2") (pintype "passive"))
      (node (ref "S256") (pin "2") (pinfunction "2_2") (pintype "passive"))
      (node (ref "S267") (pin "2") (pinfunction "2_2") (pintype "passive"))
    )
    (net (code "9") (name "/row1") (class "Default")
      (node (ref "D201") (pin "2") (pinfunction "K_2") (pintype "passive"))
      (node (ref "D203") (pin "2") (pinfunction "K_2") (pintype "passive"))
      (node (ref "D205") (pin "2") (pinfunction "K_2") (pintype "passive"))
      (node (ref "D207") (pin "2") (pinfunction "K_2") (pintype "passive"))
      (node (ref "D209") (pin "2") (pinfunction "K_2") (pintype "passive"))
      (node (ref "D211") (pin "2") (pinfunction "K_2") (pintype "passive"))
      (node (ref "D213") (pin "2") (pinfunction "K_2") (pintype "passive"))
    )
    (net (code "10") (name "/row2") (class "Default")
      (node (ref "D202") (pin "2") (pinfunction "K_2") (pintype "passive"))
      (node (ref "D204") (pin "2") (pinfunction "K_2") (pintype "passive"))
      (node (ref "D206") (pin "2") (pinfunction "K_2") (pintype "passive"))
      (node (ref "D208") (pin "2") (pinfunction "K_2") (pintype "passive"))
      (node (ref "D210") (pin "2") (pinfunction "K_2") (pintype "passive"))
      (node (ref "D212") (pin "2") (pinfunction "K_2") (pintype "passive"))
      (node (ref "D214") (pin "2") (pinfunction "K_2") (pintype "passive"))
    )
    (net (code "11") (name "/row3") (class "Default")
      (node (ref "D215") (pin "2") (pinfunction "K_2") (pintype "passive"))
      (node (ref "D217") (pin "2") (pinfunction "K_2") (pintype "passive"))
      (node (ref "D219") (pin "2") (pinfunction "K_2") (pintype "passive"))
      (node (ref "D221") (pin "2") (pinfunction "K_2") (pintype "passive"))
      (node (ref "D223") (pin "2") (pinfunction "K_2") (pintype "passive"))
      (node (ref "D225") (pin "2") (pinfunction "K_2") (pintype "passive"))
      (node (ref "D227") (pin "2") (pinfunction "K_2") (pintype "passive"))
    )
    (net (code "12") (name "/row4") (class "Default")
      (node (ref "D216") (pin "2") (pinfunction "K_2") (pintype "passive"))
      (node (ref "D218") (pin "2") (pinfunction "K_2") (pintype "passive"))
      (node (ref "D220") (pin "2") (pinfunction "K_2") (pintype "passive"))
      (node (ref "D222") (pin "2") (pinfunction "K_2") (pintype "passive"))
      (node (ref "D224") (pin "2") (pinfunction "K_2") (pintype "passive"))
      (node (ref "D226") (pin "2") (pinfunction "K_2") (pintype "passive"))
      (node (ref "D228") (pin "2") (pinfunction "K_2") (pintype "passive"))
    )
    (net (code "13") (name "/row5") (class "Default")
      (node (ref "D229") (pin "2") (pinfunction "K_2") (pintype "passive"))
      (node (ref "D231") (pin "2") (pinfunction "K_2") (pintype "passive"))
      (node (ref "D233") (pin "2") (pinfunction "K_2") (pintype "passive"))
      (node (ref "D235") (pin "2") (pinfunction "K_2") (pintype "passive"))
      (node (ref "D237") (pin "2") (pinfunction "K_2") (pintype "passive"))
      (node (ref "D239") (pin "2") (pinfunction "K_2") (pintype "passive"))
    )
    (net (code "14") (name "/row6") (class "Default")
      (node (ref "D230") (pin "2") (pinfunction "K_2") (pintype "passive"))
      (node (ref "D232") (pin "2") (pinfunction "K_2") (pintype "passive"))
      (node (ref "D234") (pin "2") (pinfunction "K_2") (pintype "passive"))
      (node (ref "D236") (pin "2") (pinfunction "K_2") (pintype "passive"))
      (node (ref "D238") (pin "2") (pinfunction "K_2") (pintype "passive"))
      (node (ref "D240") (pin "2") (pinfunction "K_2") (pintype "passive"))
      (node (ref "D242") (pin "2") (pinfunction "K_2") (pintype "passive"))
    )
    (net (code "15") (name "/row7") (class "Default")
      (node (ref "D243") (pin "2") (pinfunction "K_2") (pintype "passive"))
      (node (ref "D245") (pin "2") (pinfunction "K_2") (pintype "passive"))
      (node (ref "D247") (pin "2") (pinfunction "K_2") (pintype "passive"))
      (node (ref "D249") (pin "2") (pinfunction "K_2") (pintype "passive"))
      (node (ref "D251") (pin "2") (pinfunction "K_2") (pintype "passive"))
      (node (ref "D253") (pin "2") (pinfunction "K_2") (pintype "passive"))
      (node (ref "D255") (pin "2") (pinfunction "K_2") (pintype "passive"))
    )
    (net (code "16") (name "/row8") (class "Default")
      (node (ref "D246") (pin "2") (pinfunction "K_2") (pintype "passive"))
      (node (ref "D248") (pin "2") (pinfunction "K_2") (pintype "passive"))
      (node (ref "D250") (pin "2") (pinfunction "K_2") (pintype "passive"))
      (node (ref "D252") (pin "2") (pinfunction "K_2") (pintype "passive"))
      (node (ref "D254") (pin "2") (pinfunction "K_2") (pintype "passive"))
      (node (ref "D256") (pin "2") (pinfunction "K_2") (pintype "passive"))
    )
    (net (code "17") (name "/row9") (class "Default")
      (node (ref "D257") (pin "2") (pinfunction "K_2") (pintype "passive"))
      (node (ref "D259") (pin "2") (pinfunction "K_2") (pintype "passive"))
      (node (ref "D261") (pin "2") (pinfunction "K_2") (pintype "passive"))
      (node (ref "D265") (pin "2") (pinfunction "K_2") (pintype "passive"))
      (node (ref "D267") (pin "2") (pinfunction "K_2") (pintype "passive"))
    )
    (net (code "18") (name "/row10") (class "Default")
      (node (ref "D258") (pin "2") (pinfunction "K_2") (pintype "passive"))
      (node (ref "D264") (pin "2") (pinfunction "K_2") (pintype "passive"))
      (node (ref "D266") (pin "2") (pinfunction "K_2") (pintype "passive"))
      (node (ref "D270") (pin "2") (pinfunction "K_2") (pintype "passive"))
    )
    (net (code "19") (name "Net-(D201-A)") (class "Default")
      (node (ref "D201") (pin "1") (pinfunction "A_1") (pintype "passive"))
      (node (ref "S201") (pin "1") (pinfunction "1_1") (pintype "passive"))
    )
    (net (code "20") (name "Net-(D202-A)") (class "Default")
      (node (ref "D202") (pin "1") (pinfunction "A_1") (pintype "passive"))
      (node (ref "S202") (pin "1") (pinfunction "1_1") (pintype "passive"))
    )
    (net (code "21") (name "Net-(D203-A)") (class "Default")
      (node (ref "D203") (pin "1") (pinfunction "A_1") (pintype "passive"))
      (node (ref "S203") (pin "1") (pinfunction "1_1") (pintype "passive"))
    )
    (net (code "22") (name "Net-(D204-A)") (class "Default")
      (node (ref "D204") (pin "1") (pinfunction "A_1") (pintype "passive"))
      (node (ref "S204") (pin "1") (pinfunction "1_1") (pintype "passive"))
    )
    (net (code "23") (name "Net-(D205-A)") (class "Default")
      (node (ref "D205") (pin "1") (pinfunction "A_1") (pintype "passive"))
      (node (ref "S205") (pin "1") (pinfunction "1_1") (pintype "passive"))
    )
    (net (code "24") (name "Net-(D206-A)") (class "Default")
      (node (ref "D206") (pin "1") (pinfunction "A_1") (pintype "passive"))
      (node (ref "S206") (pin "1") (pinfunction "1_1") (pintype "passive"))
    )
    (net (code "25") (name "Net-(D207-A)") (class "Default")
      (node (ref "D207") (pin "1") (pinfunction "A_1") (pintype "passive"))
      (node (ref "S207") (pin "1") (pinfunction "1_1") (pintype "passive"))
    )
    (net (code "26") (name "Net-(D208-A)") (class "Default")
      (node (ref "D208") (pin "1") (pinfunction "A_1") (pintype "passive"))
      (node (ref "S208") (pin "1") (pinfunction "1_1") (pintype "passive"))
    )
    (net (code "27") (name "Net-(D209-A)") (class "Default")
      (node (ref "D209") (pin "1") (pinfunction "A_1") (pintype "passive"))
      (node (ref "S209") (pin "1") (pinfunction "1_1") (pintype "passive"))
    )
    (net (code "28") (name "Net-(D210-A)") (class "Default")
      (node (ref "D210") (pin "1") (pinfunction "A_1") (pintype "passive"))
      (node (ref "S210") (pin "1") (pinfunction "1_1") (pintype "passive"))
    )
    (net (code "29") (name "Net-(D211-A)") (class "Default")
      (node (ref "D211") (pin "1") (pinfunction "A_1") (pintype "passive"))
      (node (ref "S211") (pin "1") (pinfunction "1_1") (pintype "passive"))
    )
    (net (code "30") (name "Net-(D212-A)") (class "Default")
      (node (ref "D212") (pin "1") (pinfunction "A_1") (pintype "passive"))
      (node (ref "S212") (pin "1") (pinfunction "1_1") (pintype "passive"))
    )
    (net (code "31") (name "Net-(D213-A)") (class "Default")
      (node (ref "D213") (pin "1") (pinfunction "A_1") (pintype "passive"))
      (node (ref "S213") (pin "1") (pinfunction "1_1") (pintype "passive"))
    )
    (net (code "32") (name "Net-(D214-A)") (class "Default")
      (node (ref "D214") (pin "1") (pinfunction "A_1") (pintype "passive"))
      (node (ref "S214") (pin "1") (pinfunction "1_1") (pintype "passive"))
    )
    (net (code "33") (name "Net-(D215-A)") (class "Default")
      (node (ref "D215") (pin "1") (pinfunction "A_1") (pintype "passive"))
      (node (ref "S215") (pin "1") (pinfunction "1_1") (pintype "passive"))
    )
    (net (code "34") (name "Net-(D216-A)") (class "Default")
      (node (ref "D216") (pin "1") (pinfunction "A_1") (pintype "passive"))
      (node (ref "S216") (pin "1") (pinfunction "1_1") (pintype "passive"))
    )
    (net (code "35") (name "Net-(D217-A)") (class "Default")
      (node (ref "D217") (pin "1") (pinfunction "A_1") (pintype "passive"))
      (node (ref "S217") (pin "1") (pinfunction "1_1") (pintype "passive"))
    )
    (net (code "36") (name "Net-(D218-A)") (class "Default")
      (node (ref "D218") (pin "1") (pinfunction "A_1") (pintype "passive"))
      (node (ref "S218") (pin "1") (pinfunction "1_1") (pintype "passive"))
    )
    (net (code "37") (name "Net-(D219-A)") (class "Default")
      (node (ref "D219") (pin "1") (pinfunction "A_1") (pintype "passive"))
      (node (ref "S219") (pin "1") (pinfunction "1_1") (pintype "passive"))
    )
    (net (code "38") (name "Net-(D220-A)") (class "Default")
      (node (ref "D220") (pin "1") (pinfunction "A_1") (pintype "passive"))
      (node (ref "S220") (pin "1") (pinfunction "1_1") (pintype "passive"))
    )
    (net (code "39") (name "Net-(D221-A)") (class "Default")
      (node (ref "D221") (pin "1") (pinfunction "A_1") (pintype "passive"))
      (node (ref "S221") (pin "1") (pinfunction "1_1") (pintype "passive"))
    )
    (net (code "40") (name "Net-(D222-A)") (class "Default")
      (node (ref "D222") (pin "1") (pinfunction "A_1") (pintype "passive"))
      (node (ref "S222") (pin "1") (pinfunction "1_1") (pintype "passive"))
    )
    (net (code "41") (name "Net-(D223-A)") (class "Default")
      (node (ref "D223") (pin "1") (pinfunction "A_1") (pintype "passive"))
      (node (ref "S223") (pin "1") (pinfunction "1_1") (pintype "passive"))
    )
    (net (code "42") (name "Net-(D224-A)") (class "Default")
      (node (ref "D224") (pin "1") (pinfunction "A_1") (pintype "passive"))
      (node (ref "S224") (pin "1") (pinfunction "1_1") (pintype "passive"))
    )
    (net (code "43") (name "Net-(D225-A)") (class "Default")
      (node (ref "D225") (pin "1") (pinfunction "A_1") (pintype "passive"))
      (node (ref "S225") (pin "1") (pinfunction "1_1") (pintype "passive"))
    )
    (net (code "44") (name "Net-(D226-A)") (class "Default")
      (node (ref "D226") (pin "1") (pinfunction "A_1") (pintype "passive"))
      (node (ref "S226") (pin "1") (pinfunction "1_1") (pintype "passive"))
    )
    (net (code "45") (name "Net-(D227-A)") (class "Default")
      (node (ref "D227") (pin "1") (pinfunction "A_1") (pintype "passive"))
      (node (ref "S227") (pin "1") (pinfunction "1_1") (pintype "passive"))
    )
    (net (code "46") (name "Net-(D228-A)") (class "Default")
      (node (ref "D228") (pin "1") (pinfunction "A_1") (pintype "passive"))
      (node (ref "S228_1") (pin "1") (pinfunction "1_1") (pintype "passive"))
      (node (ref "S228_2") (pin "2") (pinfunction "2_2") (pintype "passive"))
    )
    (net (code "47") (name "Net-(D229-A)") (class "Default")
      (node (ref "D229") (pin "1") (pinfunction "A_1") (pintype "passive"))
      (node (ref "S229") (pin "1") (pinfunction "1_1") (pintype "passive"))
      (node (ref "S229_2") (pin "1") (pinfunction "1_1") (pintype "passive"))
    )
    (net (code "48") (name "Net-(D230-A)") (class "Default")
      (node (ref "D230") (pin "1") (pinfunction "A_1") (pintype "passive"))
      (node (ref "S230") (pin "1") (pinfunction "1_1") (pintype "passive"))
    )
    (net (code "49") (name "Net-(D231-A)") (class "Default")
      (node (ref "D231") (pin "1") (pinfunction "A_1") (pintype "passive"))
      (node (ref "S231") (pin "1") (pinfunction "1_1") (pintype "passive"))
    )
    (net (code "50") (name "Net-(D232-A)") (class "Default")
      (node (ref "D232") (pin "1") (pinfunction "A_1") (pintype "passive"))
      (node (ref "S232") (pin "1") (pinfunction "1_1") (pintype "passive"))
    )
    (net (code "51") (name "Net-(D233-A)") (class "Default")
      (node (ref "D233") (pin "1") (pinfunction "A_1") (pintype "passive"))
      (node (ref "S233") (pin "1") (pinfunction "1_1") (pintype "passive"))
    )
    (net (code "52") (name "Net-(D234-A)") (class "Default")
      (node (ref "D234") (pin "1") (pinfunction "A_1") (pintype "passive"))
      (node (ref "S234") (pin "1") (pinfunction "1_1") (pintype "passive"))
    )
    (net (code "53") (name "Net-(D235-A)") (class "Default")
      (node (ref "D235") (pin "1") (pinfunction "A_1") (pintype "passive"))
      (node (ref "S235") (pin "1") (pinfunction "1_1") (pintype "passive"))
    )
    (net (code "54") (name "Net-(D236-A)") (class "Default")
      (node (ref "D236") (pin "1") (pinfunction "A_1") (pintype "passive"))
      (node (ref "S236") (pin "1") (pinfunction "1_1") (pintype "passive"))
    )
    (net (code "55") (name "Net-(D237-A)") (class "Default")
      (node (ref "D237") (pin "1") (pinfunction "A_1") (pintype "passive"))
      (node (ref "S237") (pin "1") (pinfunction "1_1") (pintype "passive"))
    )
    (net (code "56") (name "Net-(D238-A)") (class "Default")
      (node (ref "D238") (pin "1") (pinfunction "A_1") (pintype "passive"))
      (node (ref "S238") (pin "1") (pinfunction "1_1") (pintype "passive"))
    )
    (net (code "57") (name "Net-(D239-A)") (class "Default")
      (node (ref "D239") (pin "1") (pinfunction "A_1") (pintype "passive"))
      (node (ref "S239") (pin "1") (pinfunction "1_1") (pintype "passive"))
    )
    (net (code "58") (name "Net-(D240-A)") (class "Default")
      (node (ref "D240") (pin "1") (pinfunction "A_1") (pintype "passive"))
      (node (ref "S240") (pin "1") (pinfunction "1_1") (pintype "passive"))
    )
    (net (code "59") (name "Net-(D242-A)") (class "Default")
      (node (ref "D242") (pin "1") (pinfunction "A_1") (pintype "passive"))
      (node (ref "S242") (pin "2") (pinfunction "2_2") (pintype "passive"))
    )
    (net (code "60") (name "Net-(D243-A)") (class "Default")
      (node (ref "D243") (pin "1") (pinfunction "A_1") (pintype "passive"))
      (node (ref "S243") (pin "1") (pinfunction "1_1") (pintype "passive"))
    )
    (net (code "61") (name "Net-(D245-A)") (class "Default")
      (node (ref "D245") (pin "1") (pinfunction "A_1") (pintype "passive"))
      (node (ref "S245") (pin "1") (pinfunction "1_1") (pintype "passive"))
    )
    (net (code "62") (name "Net-(D246-A)") (class "Default")
      (node (ref "D246") (pin "1") (pinfunction "A_1") (pintype "passive"))
      (node (ref "S246") (pin "1") (pinfunction "1_1") (pintype "passive"))
    )
    (net (code "63") (name "Net-(D247-A)") (class "Default")
      (node (ref "D247") (pin "1") (pinfunction "A_1") (pintype "passive"))
      (node (ref "S247") (pin "1") (pinfunction "1_1") (pintype "passive"))
    )
    (net (code "64") (name "Net-(D248-A)") (class "Default")
      (node (ref "D248") (pin "1") (pinfunction "A_1") (pintype "passive"))
      (node (ref "S248") (pin "1") (pinfunction "1_1") (pintype "passive"))
    )
    (net (code "65") (name "Net-(D249-A)") (class "Default")
      (node (ref "D249") (pin "1") (pinfunction "A_1") (pintype "passive"))
      (node (ref "S249") (pin "1") (pinfunction "1_1") (pintype "passive"))
    )
    (net (code "66") (name "Net-(D250-A)") (class "Default")
      (node (ref "D250") (pin "1") (pinfunction "A_1") (pintype "passive"))
      (node (ref "S250") (pin "1") (pinfunction "1_1") (pintype "passive"))
    )
    (net (code "67") (name "Net-(D251-A)") (class "Default")
      (node (ref "D251") (pin "1") (pinfunction "A_1") (pintype "passive"))
      (node (ref "S251") (pin "1") (pinfunction "1_1") (pintype "passive"))
    )
    (net (code "68") (name "Net-(D252-A)") (class "Default")
      (node (ref "D252") (pin "1") (pinfunction "A_1") (pintype "passive"))
      (node (ref "S252") (pin "1") (pinfunction "1_1") (pintype "passive"))
    )
    (net (code "69") (name "Net-(D253-A)") (class "Default")
      (node (ref "D253") (pin "1") (pinfunction "A_1") (pintype "passive"))
      (node (ref "S253") (pin "1") (pinfunction "1_1") (pintype "passive"))
    )
    (net (code "70") (name "Net-(D254-A)") (class "Default")
      (node (ref "D254") (pin "1") (pinfunction "A_1") (pintype "passive"))
      (node (ref "S254") (pin "1") (pinfunction "1_1") (pintype "passive"))
    )
    (net (code "71") (name "Net-(D255-A)") (class "Default")
      (node (ref "D255") (pin "1") (pinfunction "A_1") (pintype "passive"))
      (node (ref "S255") (pin "1") (pinfunction "1_1") (pintype "passive"))
    )
    (net (code "72") (name "Net-(D256-A)") (class "Default")
      (node (ref "D256") (pin "1") (pinfunction "A_1") (pintype "passive"))
      (node (ref "S256") (pin "1") (pinfunction "1_1") (pintype "passive"))
    )
    (net (code "73") (name "Net-(D257-A)") (class "Default")
      (node (ref "D257") (pin "1") (pinfunction "A_1") (pintype "passive"))
      (node (ref "S257") (pin "1") (pinfunction "1_1") (pintype "passive"))
    )
    (net (code "74") (name "Net-(D258-A)") (class "Default")
      (node (ref "D258") (pin "1") (pinfunction "A_1") (pintype "passive"))
      (node (ref "S258") (pin "1") (pinfunction "1_1") (pintype "passive"))
    )
    (net (code "75") (name "Net-(D259-A)") (class "Default")
      (node (ref "D259") (pin "1") (pinfunction "A_1") (pintype "passive"))
      (node (ref "S259") (pin "1") (pinfunction "1_1") (pintype "passive"))
    )
    (net (code "76") (name "Net-(D261-A)") (class "Default")
      (node (ref "D261") (pin "1") (pinfunction "A_1") (pintype "passive"))
      (node (ref "S261") (pin "2") (pinfunction "2_2") (pintype "passive"))
    )
    (net (code "77") (name "Net-(D264-A)") (class "Default")
      (node (ref "D264") (pin "1") (pinfunction "A_1") (pintype "passive"))
      (node (ref "S264") (pin "2") (pinfunction "2_2") (pintype "passive"))
    )
    (net (code "78") (name "Net-(D265-A)") (class "Default")
      (node (ref "D265") (pin "1") (pinfunction "A_1") (pintype "passive"))
      (node (ref "S265") (pin "1") (pinfunction "1_1") (pintype "passive"))
    )
    (net (code "79") (name "Net-(D266-A)") (class "Default")
      (node (ref "D266") (pin "1") (pinfunction "A_1") (pintype "passive"))
      (node (ref "S266") (pin "1") (pinfunction "1_1") (pintype "passive"))
    )
    (net (code "80") (name "Net-(D267-A)") (class "Default")
      (node (ref "D267") (pin "1") (pinfunction "A_1") (pintype "passive"))
      (node (ref "S267") (pin "1") (pinfunction "1_1") (pintype "passive"))
    )
    (net (code "81") (name "unconnected-(STAB1-Pad1)") (class "Default")
      (node (ref "STAB1") (pin "1") (pinfunction "1_1") (pintype "passive"))
    )
    (net (code "82") (name "unconnected-(STAB2-Pad1)") (class "Default")
      (node (ref "STAB2") (pin "1") (pinfunction "1_1") (pintype "passive"))
    )
    (net (code "83") (name "unconnected-(STAB3-Pad1)") (class "Default")
      (node (ref "STAB3") (pin "1") (pinfunction "1_1") (pintype "passive"))
    )
    (net (code "84") (name "unconnected-(STAB6-Pad1)") (class "Default")
      (node (ref "STAB6") (pin "1") (pinfunction "1_1") (pintype "passive"))
    )
  )
)
